# magBoard.net
KiCad netlist of a schematic drawn in EAGLE
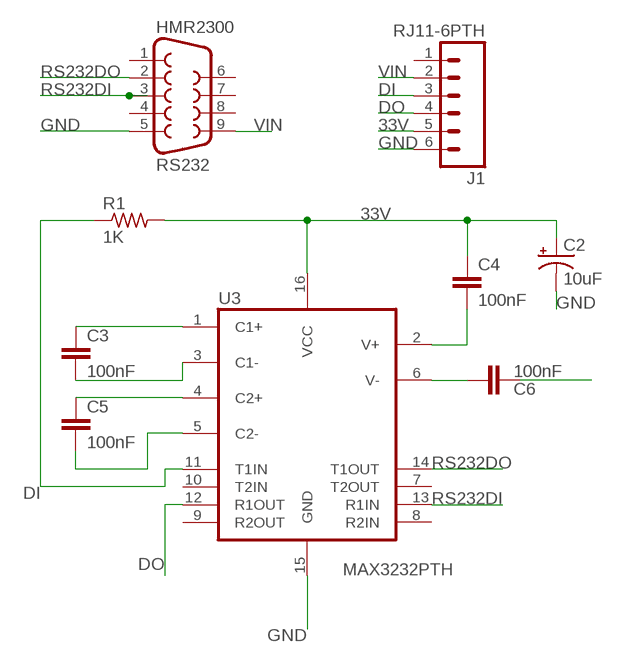
[diagram p0: schematic, sheet 1]

(export (version "E")
  (design (tool "Eeschema 10.0.6"))
  (components
    (comp (ref "C2")
      (value "10uF")
      (footprint "eagle-import:CPOL-RADIAL-10UF-25V")
      (libsource (lib "eagle-import") (part "CAP_POLPTH2"))
    )
    (comp (ref "C3")
      (value "100nF")
      (footprint "eagle-import:CAP-PTH-SMALL-KIT")
      (libsource (lib "eagle-import") (part "CAPKIT"))
    )
    (comp (ref "C4")
      (value "100nF")
      (footprint "eagle-import:CAP-PTH-SMALL-KIT")
      (libsource (lib "eagle-import") (part "CAPKIT"))
    )
    (comp (ref "C5")
      (value "100nF")
      (footprint "eagle-import:CAP-PTH-SMALL-KIT")
      (libsource (lib "eagle-import") (part "CAPKIT"))
    )
    (comp (ref "C6")
      (value "100nF")
      (footprint "eagle-import:CAP-PTH-SMALL-KIT")
      (libsource (lib "eagle-import") (part "CAPKIT"))
    )
    (comp (ref "HMR2300")
      (value "RS232")
      (footprint "eagle-import:DB9")
      (libsource (lib "eagle-import") (part "DB9FEMALE"))
    )
    (comp (ref "J1")
      (value "RJ11-6PTH")
      (footprint "eagle-import:RJ11-6")
      (libsource (lib "eagle-import") (part "RJ11-6PTH"))
    )
    (comp (ref "R1")
      (value "1K")
      (footprint "eagle-import:0204_5")
      (libsource (lib "eagle-import") (part "R-US_0204/5"))
    )
    (comp (ref "U3")
      (value "MAX3232PTH")
      (footprint "eagle-import:DIL16")
      (libsource (lib "eagle-import") (part "MAX232PTH"))
    )
  )
  (nets
    (net (code "1") (name "/33V") (class "Default")
      (node (ref "C2") (pin "1") (pinfunction "+_1") (pintype "passive"))
      (node (ref "C4") (pin "1") (pinfunction "1_1") (pintype "passive"))
      (node (ref "J1") (pin "5") (pinfunction "5_5") (pintype "passive"))
      (node (ref "R1") (pin "2") (pinfunction "2_2") (pintype "passive"))
      (node (ref "U3") (pin "16") (pinfunction "VCC_16") (pintype "bidirectional"))
    )
    (net (code "2") (name "/DI") (class "Default")
      (node (ref "J1") (pin "3") (pinfunction "3_3") (pintype "passive"))
      (node (ref "R1") (pin "1") (pinfunction "1_1") (pintype "passive"))
      (node (ref "U3") (pin "11") (pinfunction "T1IN_11") (pintype "input"))
    )
    (net (code "3") (name "/DO") (class "Default")
      (node (ref "J1") (pin "4") (pinfunction "4_4") (pintype "passive"))
      (node (ref "U3") (pin "12") (pinfunction "R1OUT_12") (pintype "output"))
    )
    (net (code "4") (name "/GND") (class "Default")
      (node (ref "C2") (pin "2") (pinfunction "-_2") (pintype "passive"))
      (node (ref "C6") (pin "2") (pinfunction "2_2") (pintype "passive"))
      (node (ref "HMR2300") (pin "5") (pinfunction "5_5") (pintype "passive"))
      (node (ref "J1") (pin "6") (pinfunction "6_6") (pintype "passive"))
      (node (ref "U3") (pin "15") (pinfunction "GND_15") (pintype "bidirectional"))
    )
    (net (code "5") (name "/RS232DI") (class "Default")
      (node (ref "HMR2300") (pin "3") (pinfunction "3_3") (pintype "passive"))
      (node (ref "U3") (pin "13") (pinfunction "R1IN_13") (pintype "input"))
    )
    (net (code "6") (name "/RS232DO") (class "Default")
      (node (ref "HMR2300") (pin "2") (pinfunction "2_2") (pintype "passive"))
      (node (ref "U3") (pin "14") (pinfunction "T1OUT_14") (pintype "output"))
    )
    (net (code "7") (name "/VIN") (class "Default")
      (node (ref "HMR2300") (pin "9") (pinfunction "9_9") (pintype "passive"))
      (node (ref "J1") (pin "2") (pinfunction "2_2") (pintype "passive"))
    )
    (net (code "8") (name "Net-(U3-C1+)") (class "Default")
      (node (ref "C3") (pin "1") (pinfunction "1_1") (pintype "passive"))
      (node (ref "U3") (pin "1") (pinfunction "C1+_1") (pintype "bidirectional"))
    )
    (net (code "9") (name "Net-(U3-C1-)") (class "Default")
      (node (ref "C3") (pin "2") (pinfunction "2_2") (pintype "passive"))
      (node (ref "U3") (pin "3") (pinfunction "C1-_3") (pintype "bidirectional"))
    )
    (net (code "10") (name "Net-(U3-C2+)") (class "Default")
      (node (ref "C5") (pin "1") (pinfunction "1_1") (pintype "passive"))
      (node (ref "U3") (pin "4") (pinfunction "C2+_4") (pintype "bidirectional"))
    )
    (net (code "11") (name "Net-(U3-C2-)") (class "Default")
      (node (ref "C5") (pin "2") (pinfunction "2_2") (pintype "passive"))
      (node (ref "U3") (pin "5") (pinfunction "C2-_5") (pintype "bidirectional"))
    )
    (net (code "12") (name "Net-(U3-V+)") (class "Default")
      (node (ref "C4") (pin "2") (pinfunction "2_2") (pintype "passive"))
      (node (ref "U3") (pin "2") (pinfunction "V+_2") (pintype "bidirectional"))
    )
    (net (code "13") (name "Net-(U3-V-)") (class "Default")
      (node (ref "C6") (pin "1") (pinfunction "1_1") (pintype "passive"))
      (node (ref "U3") (pin "6") (pinfunction "V-_6") (pintype "bidirectional"))
    )
    (net (code "14") (name "unconnected-(HMR2300-Pad1)") (class "Default")
      (node (ref "HMR2300") (pin "1") (pinfunction "1_1") (pintype "passive"))
    )
    (net (code "15") (name "unconnected-(HMR2300-Pad4)") (class "Default")
      (node (ref "HMR2300") (pin "4") (pinfunction "4_4") (pintype "passive"))
    )
    (net (code "16") (name "unconnected-(HMR2300-Pad6)") (class "Default")
      (node (ref "HMR2300") (pin "6") (pinfunction "6_6") (pintype "passive"))
    )
    (net (code "17") (name "unconnected-(HMR2300-Pad7)") (class "Default")
      (node (ref "HMR2300") (pin "7") (pinfunction "7_7") (pintype "passive"))
    )
    (net (code "18") (name "unconnected-(HMR2300-Pad8)") (class "Default")
      (node (ref "HMR2300") (pin "8") (pinfunction "8_8") (pintype "passive"))
    )
    (net (code "19") (name "unconnected-(J1-Pad1)") (class "Default")
      (node (ref "J1") (pin "1") (pinfunction "1_1") (pintype "passive"))
    )
    (net (code "20") (name "unconnected-(U3-R2IN-Pad8)") (class "Default")
      (node (ref "U3") (pin "8") (pinfunction "R2IN_8") (pintype "input"))
    )
    (net (code "21") (name "unconnected-(U3-R2OUT-Pad9)") (class "Default")
      (node (ref "U3") (pin "9") (pinfunction "R2OUT_9") (pintype "output"))
    )
    (net (code "22") (name "unconnected-(U3-T2IN-Pad10)") (class "Default")
      (node (ref "U3") (pin "10") (pinfunction "T2IN_10") (pintype "input"))
    )
    (net (code "23") (name "unconnected-(U3-T2OUT-Pad7)") (class "Default")
      (node (ref "U3") (pin "7") (pinfunction "T2OUT_7") (pintype "output"))
    )
  )
)
